# RTM_Connectors.net
KiCad netlist of a schematic drawn in Altium Designer
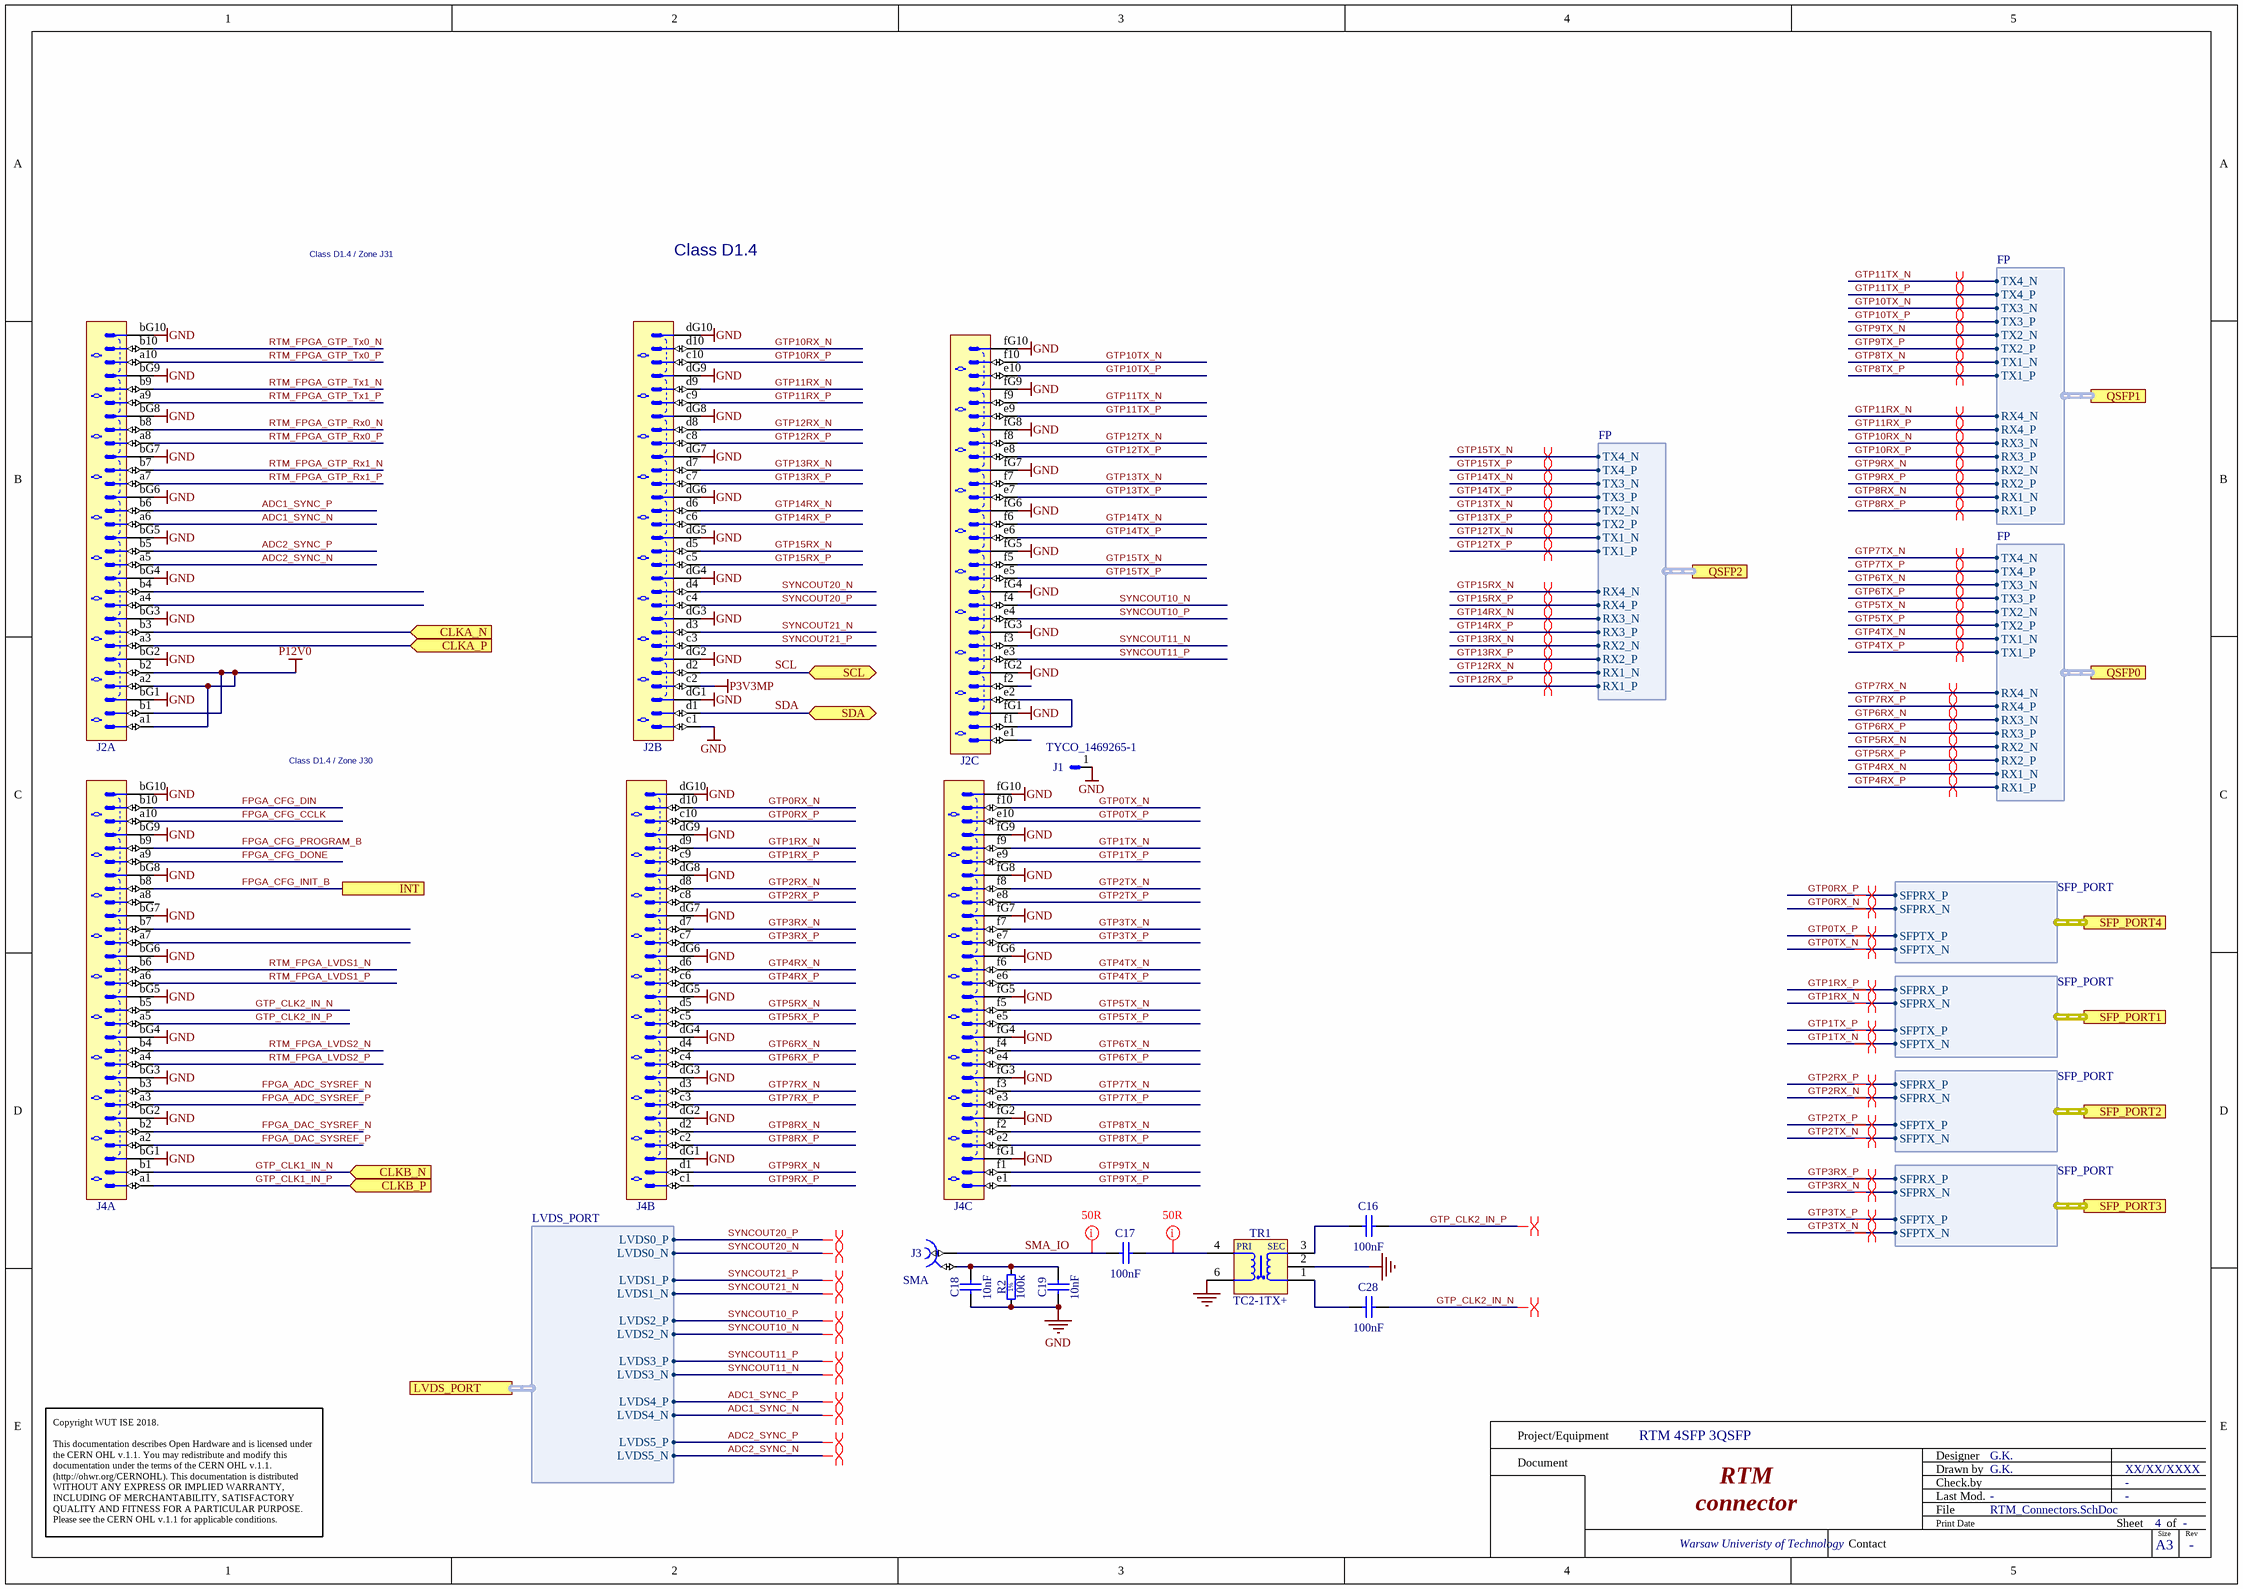
[diagram p0: RTM_Connectors.SchDoc]

(export (version "E")
  (design (tool "Eeschema 10.0.6"))
  (components
    (comp (ref "C16")
      (value "100nF")
      (footprint "CAPC0603X33N")
      (description "Non-polarised capacitor")
      (fields
        (field (name "PART NUMBER") "CC0201_100NF_6.3V_10%_X5R")
        (field (name "VOLTAGE") "6.3V")
        (field (name "AUTHOR") "CERN DEM JLC")
      )
      (libsource (lib "Capacitors") (part "Capacitor - non polarized"))
    )
    (comp (ref "C17")
      (value "100nF")
      (footprint "CAPC0603X33N")
      (description "Non-polarised capacitor")
      (fields
        (field (name "PART NUMBER") "CC0201_100NF_6.3V_10%_X5R")
        (field (name "VOLTAGE") "6.3V")
        (field (name "AUTHOR") "CERN DEM JLC")
      )
      (libsource (lib "Capacitors") (part "Capacitor - non polarized"))
    )
    (comp (ref "C18")
      (value "10nF")
      (footprint "CAPC1005X55N")
      (description "Non-polarised capacitor")
      (fields
        (field (name "PART NUMBER") "CC0402_10NF_16V_10%_X7R")
        (field (name "VOLTAGE") "16V")
        (field (name "AUTHOR") "CERN DEM JLC")
      )
      (libsource (lib "Capacitors") (part "Capacitor - non polarized"))
    )
    (comp (ref "C19")
      (value "10nF")
      (footprint "CAPC1005X55N")
      (description "Non-polarised capacitor")
      (fields
        (field (name "PART NUMBER") "CC0402_10NF_16V_10%_X7R")
        (field (name "VOLTAGE") "16V")
        (field (name "AUTHOR") "CERN DEM JLC")
      )
      (libsource (lib "Capacitors") (part "Capacitor - non polarized"))
    )
    (comp (ref "C28")
      (value "100nF")
      (footprint "CAPC0603X33N")
      (description "Non-polarised capacitor")
      (fields
        (field (name "PART NUMBER") "CC0201_100NF_6.3V_10%_X5R")
        (field (name "VOLTAGE") "6.3V")
        (field (name "AUTHOR") "CERN DEM JLC")
      )
      (libsource (lib "Capacitors") (part "Capacitor - non polarized"))
    )
    (comp (ref "J1")
      (value "TYCO_1469265-1")
      (footprint "TYCO_1469265-1")
      (description "Single Pin Male")
      (libsource (lib "Connectors") (part "Single Pin Male"))
    )
    (comp (ref "J2")
      (value "Advanced TCA")
      (footprint "TYCO_6469183-1")
      (description "Connector 60 ATCA Male 30 Pairs (60 Signals) + 3x10 Ground")
      (fields
        (field (name "PART NUMBER") "TYCO_6469183-1")
        (field (name "MANUFACTURER") "TYCO ELECTRONICS")
        (field (name "AUTHOR") "CERN DEM JLC")
      )
      (libsource (lib "Connectors") (part "Connector ATCA 60+30 Male"))
    )
    (comp (ref "J3")
      (value "SMA")
      (footprint "AMPHENOL_132203")
      (fields
        (field (name "PART NUMBER") "AMPHENOL_132203")
        (field (name "MANUFACTURER") "AMPHENOL")
        (field (name "MANUFACTURER PART NUMBER") "132203")
        (field (name "AUTHOR") "CERN DEM MR")
      )
      (libsource (lib "Connectors") (part "Coax_1Female_1Shield"))
    )
    (comp (ref "J4")
      (value "Advanced TCA")
      (footprint "TYCO_6469183-1")
      (description "Connector 60 ATCA Male 30 Pairs (60 Signals) + 3x10 Ground")
      (fields
        (field (name "PART NUMBER") "TYCO_6469183-1")
        (field (name "MANUFACTURER") "TYCO ELECTRONICS")
        (field (name "AUTHOR") "CERN DEM JLC")
      )
      (libsource (lib "Connectors") (part "Connector ATCA 60+30 Male"))
    )
    (comp (ref "R2")
      (value "100k")
      (footprint "RESC1005X40N")
      (description "Resistor - 1%")
      (fields
        (field (name "PART NUMBER") "R0402_100K_1%_0.0625W_100PPM")
        (field (name "MANUFACTURER") "GENERIC")
        (field (name "AUTHOR") "CERN DEM JLC")
      )
      (libsource (lib "Resistors") (part "Resistor - 1%"))
    )
    (comp (ref "TR1")
      (value "TC2-1TX+")
      (footprint "XFMR_MINI-CIRCUITS_AT1521")
      (description "50 Ohm 3 to 300MHz RF Transformers")
      (fields (field (name "MANUFACTURER") "MINI-CIRCUITS"))
      (libsource (lib "Schlib1") (part "XFMR_MINI-CIRCUITS_TC2-1TX+"))
    )
  )
  (nets
    (net (code "4") (name "/ADC1_SYNC_N") (class "Default")
      (node (ref "J2") (pin "a6") (pinfunction "a6_a6") (pintype "bidirectional"))
    )
    (net (code "5") (name "/ADC1_SYNC_P") (class "Default")
      (node (ref "J2") (pin "b6") (pinfunction "b6_b6") (pintype "bidirectional"))
    )
    (net (code "6") (name "/ADC2_SYNC_N") (class "Default")
      (node (ref "J2") (pin "a5") (pinfunction "a5_a5") (pintype "bidirectional"))
    )
    (net (code "7") (name "/ADC2_SYNC_P") (class "Default")
      (node (ref "J2") (pin "b5") (pinfunction "b5_b5") (pintype "bidirectional"))
    )
    (net (code "8") (name "/CLKA_N") (class "Default")
      (node (ref "J2") (pin "b3") (pinfunction "b3_b3") (pintype "bidirectional"))
    )
    (net (code "9") (name "/CLKA_P") (class "Default")
      (node (ref "J2") (pin "a3") (pinfunction "a3_a3") (pintype "bidirectional"))
    )
    (net (code "10") (name "/FPGA_ADC_SYSREF_N") (class "Default")
      (node (ref "J4") (pin "b3") (pinfunction "b3_b3") (pintype "bidirectional"))
    )
    (net (code "11") (name "/FPGA_ADC_SYSREF_P") (class "Default")
      (node (ref "J4") (pin "a3") (pinfunction "a3_a3") (pintype "bidirectional"))
    )
    (net (code "12") (name "/FPGA_CFG_CCLK") (class "Default")
      (node (ref "J4") (pin "a10") (pinfunction "a10_a10") (pintype "bidirectional"))
    )
    (net (code "13") (name "/FPGA_CFG_DIN") (class "Default")
      (node (ref "J4") (pin "b10") (pinfunction "b10_b10") (pintype "bidirectional"))
    )
    (net (code "14") (name "/FPGA_CFG_DONE") (class "Default")
      (node (ref "J4") (pin "a9") (pinfunction "a9_a9") (pintype "bidirectional"))
    )
    (net (code "15") (name "/FPGA_CFG_INIT_B") (class "Default")
      (node (ref "J4") (pin "b8") (pinfunction "b8_b8") (pintype "bidirectional"))
    )
    (net (code "16") (name "/FPGA_CFG_PROGRAM_B") (class "Default")
      (node (ref "J4") (pin "b9") (pinfunction "b9_b9") (pintype "bidirectional"))
    )
    (net (code "17") (name "/FPGA_DAC_SYSREF_N") (class "Default")
      (node (ref "J4") (pin "b2") (pinfunction "b2_b2") (pintype "bidirectional"))
    )
    (net (code "18") (name "/FPGA_DAC_SYSREF_P") (class "Default")
      (node (ref "J4") (pin "a2") (pinfunction "a2_a2") (pintype "bidirectional"))
    )
    (net (code "19") (name "/GTP0RX_N") (class "Default")
      (node (ref "J4") (pin "d10") (pinfunction "d10_d10") (pintype "bidirectional"))
    )
    (net (code "20") (name "/GTP0RX_P") (class "Default")
      (node (ref "J4") (pin "c10") (pinfunction "c10_c10") (pintype "bidirectional"))
    )
    (net (code "21") (name "/GTP0TX_N") (class "Default")
      (node (ref "J4") (pin "f10") (pinfunction "f10_f10") (pintype "bidirectional"))
    )
    (net (code "22") (name "/GTP0TX_P") (class "Default")
      (node (ref "J4") (pin "e10") (pinfunction "e10_e10") (pintype "bidirectional"))
    )
    (net (code "23") (name "/GTP1RX_N") (class "Default")
      (node (ref "J4") (pin "d9") (pinfunction "d9_d9") (pintype "bidirectional"))
    )
    (net (code "24") (name "/GTP1RX_P") (class "Default")
      (node (ref "J4") (pin "c9") (pinfunction "c9_c9") (pintype "bidirectional"))
    )
    (net (code "25") (name "/GTP1TX_N") (class "Default")
      (node (ref "J4") (pin "f9") (pinfunction "f9_f9") (pintype "bidirectional"))
    )
    (net (code "26") (name "/GTP1TX_P") (class "Default")
      (node (ref "J4") (pin "e9") (pinfunction "e9_e9") (pintype "bidirectional"))
    )
    (net (code "27") (name "/GTP2RX_N") (class "Default")
      (node (ref "J4") (pin "d8") (pinfunction "d8_d8") (pintype "bidirectional"))
    )
    (net (code "28") (name "/GTP2RX_P") (class "Default")
      (node (ref "J4") (pin "c8") (pinfunction "c8_c8") (pintype "bidirectional"))
    )
    (net (code "29") (name "/GTP2TX_N") (class "Default")
      (node (ref "J4") (pin "f8") (pinfunction "f8_f8") (pintype "bidirectional"))
    )
    (net (code "30") (name "/GTP2TX_P") (class "Default")
      (node (ref "J4") (pin "e8") (pinfunction "e8_e8") (pintype "bidirectional"))
    )
    (net (code "31") (name "/GTP3RX_N") (class "Default")
      (node (ref "J4") (pin "d7") (pinfunction "d7_d7") (pintype "bidirectional"))
    )
    (net (code "32") (name "/GTP3RX_P") (class "Default")
      (node (ref "J4") (pin "c7") (pinfunction "c7_c7") (pintype "bidirectional"))
    )
    (net (code "33") (name "/GTP3TX_N") (class "Default")
      (node (ref "J4") (pin "f7") (pinfunction "f7_f7") (pintype "bidirectional"))
    )
    (net (code "34") (name "/GTP3TX_P") (class "Default")
      (node (ref "J4") (pin "e7") (pinfunction "e7_e7") (pintype "bidirectional"))
    )
    (net (code "35") (name "/GTP4RX_N") (class "Default")
      (node (ref "J4") (pin "d6") (pinfunction "d6_d6") (pintype "bidirectional"))
    )
    (net (code "36") (name "/GTP4RX_P") (class "Default")
      (node (ref "J4") (pin "c6") (pinfunction "c6_c6") (pintype "bidirectional"))
    )
    (net (code "37") (name "/GTP4TX_N") (class "Default")
      (node (ref "J4") (pin "f6") (pinfunction "f6_f6") (pintype "bidirectional"))
    )
    (net (code "38") (name "/GTP4TX_P") (class "Default")
      (node (ref "J4") (pin "e6") (pinfunction "e6_e6") (pintype "bidirectional"))
    )
    (net (code "39") (name "/GTP5RX_N") (class "Default")
      (node (ref "J4") (pin "d5") (pinfunction "d5_d5") (pintype "bidirectional"))
    )
    (net (code "40") (name "/GTP5RX_P") (class "Default")
      (node (ref "J4") (pin "c5") (pinfunction "c5_c5") (pintype "bidirectional"))
    )
    (net (code "41") (name "/GTP5TX_N") (class "Default")
      (node (ref "J4") (pin "f5") (pinfunction "f5_f5") (pintype "bidirectional"))
    )
    (net (code "42") (name "/GTP5TX_P") (class "Default")
      (node (ref "J4") (pin "e5") (pinfunction "e5_e5") (pintype "bidirectional"))
    )
    (net (code "43") (name "/GTP6RX_N") (class "Default")
      (node (ref "J4") (pin "d4") (pinfunction "d4_d4") (pintype "bidirectional"))
    )
    (net (code "44") (name "/GTP6RX_P") (class "Default")
      (node (ref "J4") (pin "c4") (pinfunction "c4_c4") (pintype "bidirectional"))
    )
    (net (code "45") (name "/GTP6TX_N") (class "Default")
      (node (ref "J4") (pin "f4") (pinfunction "f4_f4") (pintype "bidirectional"))
    )
    (net (code "46") (name "/GTP6TX_P") (class "Default")
      (node (ref "J4") (pin "e4") (pinfunction "e4_e4") (pintype "bidirectional"))
    )
    (net (code "47") (name "/GTP7RX_N") (class "Default")
      (node (ref "J4") (pin "d3") (pinfunction "d3_d3") (pintype "bidirectional"))
    )
    (net (code "48") (name "/GTP7RX_P") (class "Default")
      (node (ref "J4") (pin "c3") (pinfunction "c3_c3") (pintype "bidirectional"))
    )
    (net (code "49") (name "/GTP7TX_N") (class "Default")
      (node (ref "J4") (pin "f3") (pinfunction "f3_f3") (pintype "bidirectional"))
    )
    (net (code "50") (name "/GTP7TX_P") (class "Default")
      (node (ref "J4") (pin "e3") (pinfunction "e3_e3") (pintype "bidirectional"))
    )
    (net (code "51") (name "/GTP8RX_N") (class "Default")
      (node (ref "J4") (pin "d2") (pinfunction "d2_d2") (pintype "bidirectional"))
    )
    (net (code "52") (name "/GTP8RX_P") (class "Default")
      (node (ref "J4") (pin "c2") (pinfunction "c2_c2") (pintype "bidirectional"))
    )
    (net (code "53") (name "/GTP8TX_N") (class "Default")
      (node (ref "J4") (pin "f2") (pinfunction "f2_f2") (pintype "bidirectional"))
    )
    (net (code "54") (name "/GTP8TX_P") (class "Default")
      (node (ref "J4") (pin "e2") (pinfunction "e2_e2") (pintype "bidirectional"))
    )
    (net (code "55") (name "/GTP9RX_N") (class "Default")
      (node (ref "J4") (pin "d1") (pinfunction "d1_d1") (pintype "bidirectional"))
    )
    (net (code "56") (name "/GTP9RX_P") (class "Default")
      (node (ref "J4") (pin "c1") (pinfunction "c1_c1") (pintype "bidirectional"))
    )
    (net (code "57") (name "/GTP9TX_N") (class "Default")
      (node (ref "J4") (pin "f1") (pinfunction "f1_f1") (pintype "bidirectional"))
    )
    (net (code "58") (name "/GTP9TX_P") (class "Default")
      (node (ref "J4") (pin "e1") (pinfunction "e1_e1") (pintype "bidirectional"))
    )
    (net (code "59") (name "/GTP10RX_N") (class "Default")
      (node (ref "J2") (pin "d10") (pinfunction "d10_d10") (pintype "bidirectional"))
    )
    (net (code "60") (name "/GTP10RX_P") (class "Default")
      (node (ref "J2") (pin "c10") (pinfunction "c10_c10") (pintype "bidirectional"))
    )
    (net (code "61") (name "/GTP10TX_N") (class "Default")
      (node (ref "J2") (pin "f10") (pinfunction "f10_f10") (pintype "bidirectional"))
    )
    (net (code "62") (name "/GTP10TX_P") (class "Default")
      (node (ref "J2") (pin "e10") (pinfunction "e10_e10") (pintype "bidirectional"))
    )
    (net (code "63") (name "/GTP11RX_N") (class "Default")
      (node (ref "J2") (pin "d9") (pinfunction "d9_d9") (pintype "bidirectional"))
    )
    (net (code "64") (name "/GTP11RX_P") (class "Default")
      (node (ref "J2") (pin "c9") (pinfunction "c9_c9") (pintype "bidirectional"))
    )
    (net (code "65") (name "/GTP11TX_N") (class "Default")
      (node (ref "J2") (pin "f9") (pinfunction "f9_f9") (pintype "bidirectional"))
    )
    (net (code "66") (name "/GTP11TX_P") (class "Default")
      (node (ref "J2") (pin "e9") (pinfunction "e9_e9") (pintype "bidirectional"))
    )
    (net (code "67") (name "/GTP12RX_N") (class "Default")
      (node (ref "J2") (pin "d8") (pinfunction "d8_d8") (pintype "bidirectional"))
    )
    (net (code "68") (name "/GTP12RX_P") (class "Default")
      (node (ref "J2") (pin "c8") (pinfunction "c8_c8") (pintype "bidirectional"))
    )
    (net (code "69") (name "/GTP12TX_N") (class "Default")
      (node (ref "J2") (pin "f8") (pinfunction "f8_f8") (pintype "bidirectional"))
    )
    (net (code "70") (name "/GTP12TX_P") (class "Default")
      (node (ref "J2") (pin "e8") (pinfunction "e8_e8") (pintype "bidirectional"))
    )
    (net (code "71") (name "/GTP13RX_N") (class "Default")
      (node (ref "J2") (pin "d7") (pinfunction "d7_d7") (pintype "bidirectional"))
    )
    (net (code "72") (name "/GTP13RX_P") (class "Default")
      (node (ref "J2") (pin "c7") (pinfunction "c7_c7") (pintype "bidirectional"))
    )
    (net (code "73") (name "/GTP13TX_N") (class "Default")
      (node (ref "J2") (pin "f7") (pinfunction "f7_f7") (pintype "bidirectional"))
    )
    (net (code "74") (name "/GTP13TX_P") (class "Default")
      (node (ref "J2") (pin "e7") (pinfunction "e7_e7") (pintype "bidirectional"))
    )
    (net (code "75") (name "/GTP14RX_N") (class "Default")
      (node (ref "J2") (pin "d6") (pinfunction "d6_d6") (pintype "bidirectional"))
    )
    (net (code "76") (name "/GTP14RX_P") (class "Default")
      (node (ref "J2") (pin "c6") (pinfunction "c6_c6") (pintype "bidirectional"))
    )
    (net (code "77") (name "/GTP14TX_N") (class "Default")
      (node (ref "J2") (pin "f6") (pinfunction "f6_f6") (pintype "bidirectional"))
    )
    (net (code "78") (name "/GTP14TX_P") (class "Default")
      (node (ref "J2") (pin "e6") (pinfunction "e6_e6") (pintype "bidirectional"))
    )
    (net (code "79") (name "/GTP15RX_N") (class "Default")
      (node (ref "J2") (pin "d5") (pinfunction "d5_d5") (pintype "bidirectional"))
    )
    (net (code "80") (name "/GTP15RX_P") (class "Default")
      (node (ref "J2") (pin "c5") (pinfunction "c5_c5") (pintype "bidirectional"))
    )
    (net (code "81") (name "/GTP15TX_N") (class "Default")
      (node (ref "J2") (pin "f5") (pinfunction "f5_f5") (pintype "bidirectional"))
    )
    (net (code "82") (name "/GTP15TX_P") (class "Default")
      (node (ref "J2") (pin "e5") (pinfunction "e5_e5") (pintype "bidirectional"))
    )
    (net (code "83") (name "/GTP_CLK1_IN_N") (class "Default")
      (node (ref "J4") (pin "b1") (pinfunction "b1_b1") (pintype "bidirectional"))
    )
    (net (code "84") (name "/GTP_CLK1_IN_P") (class "Default")
      (node (ref "J4") (pin "a1") (pinfunction "a1_a1") (pintype "bidirectional"))
    )
    (net (code "85") (name "/GTP_CLK2_IN_N") (class "Default")
      (node (ref "C28") (pin "2") (pinfunction "2_2") (pintype "passive"))
      (node (ref "J4") (pin "b5") (pinfunction "b5_b5") (pintype "bidirectional"))
    )
    (net (code "86") (name "/GTP_CLK2_IN_P") (class "Default")
      (node (ref "C16") (pin "2") (pinfunction "2_2") (pintype "passive"))
      (node (ref "J4") (pin "a5") (pinfunction "a5_a5") (pintype "bidirectional"))
    )
    (net (code "88") (name "/RTM_FPGA_GTP_Rx0_N") (class "Default")
      (node (ref "J2") (pin "b8") (pinfunction "b8_b8") (pintype "bidirectional"))
    )
    (net (code "89") (name "/RTM_FPGA_GTP_Rx0_P") (class "Default")
      (node (ref "J2") (pin "a8") (pinfunction "a8_a8") (pintype "bidirectional"))
    )
    (net (code "90") (name "/RTM_FPGA_GTP_Rx1_N") (class "Default")
      (node (ref "J2") (pin "b7") (pinfunction "b7_b7") (pintype "bidirectional"))
    )
    (net (code "91") (name "/RTM_FPGA_GTP_Rx1_P") (class "Default")
      (node (ref "J2") (pin "a7") (pinfunction "a7_a7") (pintype "bidirectional"))
    )
    (net (code "92") (name "/RTM_FPGA_GTP_Tx0_N") (class "Default")
      (node (ref "J2") (pin "b10") (pinfunction "b10_b10") (pintype "bidirectional"))
    )
    (net (code "93") (name "/RTM_FPGA_GTP_Tx0_P") (class "Default")
      (node (ref "J2") (pin "a10") (pinfunction "a10_a10") (pintype "bidirectional"))
    )
    (net (code "94") (name "/RTM_FPGA_GTP_Tx1_N") (class "Default")
      (node (ref "J2") (pin "b9") (pinfunction "b9_b9") (pintype "bidirectional"))
    )
    (net (code "95") (name "/RTM_FPGA_GTP_Tx1_P") (class "Default")
      (node (ref "J2") (pin "a9") (pinfunction "a9_a9") (pintype "bidirectional"))
    )
    (net (code "96") (name "/RTM_FPGA_LVDS1_N") (class "Default")
      (node (ref "J4") (pin "b6") (pinfunction "b6_b6") (pintype "bidirectional"))
    )
    (net (code "97") (name "/RTM_FPGA_LVDS1_P") (class "Default")
      (node (ref "J4") (pin "a6") (pinfunction "a6_a6") (pintype "bidirectional"))
    )
    (net (code "98") (name "/RTM_FPGA_LVDS2_N") (class "Default")
      (node (ref "J4") (pin "b4") (pinfunction "b4_b4") (pintype "bidirectional"))
    )
    (net (code "99") (name "/RTM_FPGA_LVDS2_P") (class "Default")
      (node (ref "J4") (pin "a4") (pinfunction "a4_a4") (pintype "bidirectional"))
    )
    (net (code "100") (name "/SCL") (class "Default")
      (node (ref "J2") (pin "d2") (pinfunction "d2_d2") (pintype "bidirectional"))
    )
    (net (code "101") (name "/SDA") (class "Default")
      (node (ref "J2") (pin "d1") (pinfunction "d1_d1") (pintype "bidirectional"))
    )
    (net (code "102") (name "/SMA_IO") (class "Default")
      (node (ref "C17") (pin "1") (pinfunction "1_1") (pintype "passive"))
      (node (ref "J3") (pin "1") (pinfunction "1_1") (pintype "bidirectional"))
    )
    (net (code "103") (name "/SYNCOUT10_N") (class "Default")
      (node (ref "J2") (pin "f4") (pinfunction "f4_f4") (pintype "bidirectional"))
    )
    (net (code "104") (name "/SYNCOUT10_P") (class "Default")
      (node (ref "J2") (pin "e4") (pinfunction "e4_e4") (pintype "bidirectional"))
    )
    (net (code "105") (name "/SYNCOUT11_N") (class "Default")
      (node (ref "J2") (pin "f3") (pinfunction "f3_f3") (pintype "bidirectional"))
    )
    (net (code "106") (name "/SYNCOUT11_P") (class "Default")
      (node (ref "J2") (pin "e3") (pinfunction "e3_e3") (pintype "bidirectional"))
    )
    (net (code "107") (name "/SYNCOUT20_N") (class "Default")
      (node (ref "J2") (pin "d4") (pinfunction "d4_d4") (pintype "bidirectional"))
    )
    (net (code "108") (name "/SYNCOUT20_P") (class "Default")
      (node (ref "J2") (pin "c4") (pinfunction "c4_c4") (pintype "bidirectional"))
    )
    (net (code "109") (name "/SYNCOUT21_N") (class "Default")
      (node (ref "J2") (pin "d3") (pinfunction "d3_d3") (pintype "bidirectional"))
    )
    (net (code "110") (name "/SYNCOUT21_P") (class "Default")
      (node (ref "J2") (pin "c3") (pinfunction "c3_c3") (pintype "bidirectional"))
    )
    (net (code "114") (name "GND") (class "Default")
      (node (ref "C18") (pin "1") (pinfunction "1_1") (pintype "passive"))
      (node (ref "C19") (pin "1") (pinfunction "1_1") (pintype "passive"))
      (node (ref "J1") (pin "1") (pinfunction "1_1") (pintype "bidirectional"))
      (node (ref "J2") (pin "bG1") (pinfunction "bG1_bG1") (pintype "power_in"))
      (node (ref "J2") (pin "bG10") (pinfunction "bG10_bG10") (pintype "power_in"))
      (node (ref "J2") (pin "bG2") (pinfunction "bG2_bG2") (pintype "power_in"))
      (node (ref "J2") (pin "bG3") (pinfunction "bG3_bG3") (pintype "power_in"))
      (node (ref "J2") (pin "bG4") (pinfunction "bG4_bG4") (pintype "power_in"))
      (node (ref "J2") (pin "bG5") (pinfunction "bG5_bG5") (pintype "power_in"))
      (node (ref "J2") (pin "bG6") (pinfunction "bG6_bG6") (pintype "power_in"))
      (node (ref "J2") (pin "bG7") (pinfunction "bG7_bG7") (pintype "power_in"))
      (node (ref "J2") (pin "bG8") (pinfunction "bG8_bG8") (pintype "power_in"))
      (node (ref "J2") (pin "bG9") (pinfunction "bG9_bG9") (pintype "power_in"))
      (node (ref "J2") (pin "c1") (pinfunction "c1_c1") (pintype "bidirectional"))
      (node (ref "J2") (pin "dG1") (pinfunction "dG1_dG1") (pintype "power_in"))
      (node (ref "J2") (pin "dG10") (pinfunction "dG10_dG10") (pintype "power_in"))
      (node (ref "J2") (pin "dG2") (pinfunction "dG2_dG2") (pintype "power_in"))
      (node (ref "J2") (pin "dG3") (pinfunction "dG3_dG3") (pintype "power_in"))
      (node (ref "J2") (pin "dG4") (pinfunction "dG4_dG4") (pintype "power_in"))
      (node (ref "J2") (pin "dG5") (pinfunction "dG5_dG5") (pintype "power_in"))
      (node (ref "J2") (pin "dG6") (pinfunction "dG6_dG6") (pintype "power_in"))
      (node (ref "J2") (pin "dG7") (pinfunction "dG7_dG7") (pintype "power_in"))
      (node (ref "J2") (pin "dG8") (pinfunction "dG8_dG8") (pintype "power_in"))
      (node (ref "J2") (pin "dG9") (pinfunction "dG9_dG9") (pintype "power_in"))
      (node (ref "J2") (pin "fG1") (pinfunction "fG1_fG1") (pintype "power_in"))
      (node (ref "J2") (pin "fG10") (pinfunction "fG10_fG10") (pintype "power_in"))
      (node (ref "J2") (pin "fG2") (pinfunction "fG2_fG2") (pintype "power_in"))
      (node (ref "J2") (pin "fG3") (pinfunction "fG3_fG3") (pintype "power_in"))
      (node (ref "J2") (pin "fG4") (pinfunction "fG4_fG4") (pintype "power_in"))
      (node (ref "J2") (pin "fG5") (pinfunction "fG5_fG5") (pintype "power_in"))
      (node (ref "J2") (pin "fG6") (pinfunction "fG6_fG6") (pintype "power_in"))
      (node (ref "J2") (pin "fG7") (pinfunction "fG7_fG7") (pintype "power_in"))
      (node (ref "J2") (pin "fG8") (pinfunction "fG8_fG8") (pintype "power_in"))
      (node (ref "J2") (pin "fG9") (pinfunction "fG9_fG9") (pintype "power_in"))
      (node (ref "J4") (pin "bG1") (pinfunction "bG1_bG1") (pintype "power_in"))
      (node (ref "J4") (pin "bG10") (pinfunction "bG10_bG10") (pintype "power_in"))
      (node (ref "J4") (pin "bG2") (pinfunction "bG2_bG2") (pintype "power_in"))
      (node (ref "J4") (pin "bG3") (pinfunction "bG3_bG3") (pintype "power_in"))
      (node (ref "J4") (pin "bG4") (pinfunction "bG4_bG4") (pintype "power_in"))
      (node (ref "J4") (pin "bG5") (pinfunction "bG5_bG5") (pintype "power_in"))
      (node (ref "J4") (pin "bG6") (pinfunction "bG6_bG6") (pintype "power_in"))
      (node (ref "J4") (pin "bG7") (pinfunction "bG7_bG7") (pintype "power_in"))
      (node (ref "J4") (pin "bG8") (pinfunction "bG8_bG8") (pintype "power_in"))
      (node (ref "J4") (pin "bG9") (pinfunction "bG9_bG9") (pintype "power_in"))
      (node (ref "J4") (pin "dG1") (pinfunction "dG1_dG1") (pintype "power_in"))
      (node (ref "J4") (pin "dG10") (pinfunction "dG10_dG10") (pintype "power_in"))
      (node (ref "J4") (pin "dG2") (pinfunction "dG2_dG2") (pintype "power_in"))
      (node (ref "J4") (pin "dG3") (pinfunction "dG3_dG3") (pintype "power_in"))
      (node (ref "J4") (pin "dG4") (pinfunction "dG4_dG4") (pintype "power_in"))
      (node (ref "J4") (pin "dG5") (pinfunction "dG5_dG5") (pintype "power_in"))
      (node (ref "J4") (pin "dG6") (pinfunction "dG6_dG6") (pintype "power_in"))
      (node (ref "J4") (pin "dG7") (pinfunction "dG7_dG7") (pintype "power_in"))
      (node (ref "J4") (pin "dG8") (pinfunction "dG8_dG8") (pintype "power_in"))
      (node (ref "J4") (pin "dG9") (pinfunction "dG9_dG9") (pintype "power_in"))
      (node (ref "J4") (pin "fG1") (pinfunction "fG1_fG1") (pintype "power_in"))
      (node (ref "J4") (pin "fG10") (pinfunction "fG10_fG10") (pintype "power_in"))
      (node (ref "J4") (pin "fG2") (pinfunction "fG2_fG2") (pintype "power_in"))
      (node (ref "J4") (pin "fG3") (pinfunction "fG3_fG3") (pintype "power_in"))
      (node (ref "J4") (pin "fG4") (pinfunction "fG4_fG4") (pintype "power_in"))
      (node (ref "J4") (pin "fG5") (pinfunction "fG5_fG5") (pintype "power_in"))
      (node (ref "J4") (pin "fG6") (pinfunction "fG6_fG6") (pintype "power_in"))
      (node (ref "J4") (pin "fG7") (pinfunction "fG7_fG7") (pintype "power_in"))
      (node (ref "J4") (pin "fG8") (pinfunction "fG8_fG8") (pintype "power_in"))
      (node (ref "J4") (pin "fG9") (pinfunction "fG9_fG9") (pintype "power_in"))
      (node (ref "R2") (pin "1") (pinfunction "1_1") (pintype "passive"))
      (node (ref "TR1") (pin "2") (pinfunction "NU_2") (pintype "passive"))
      (node (ref "TR1") (pin "6") (pinfunction "PDOT_6") (pintype "passive"))
    )
    (net (code "115") (name "Net-(C18-Pad2)") (class "Default")
      (node (ref "C18") (pin "2") (pinfunction "2_2") (pintype "passive"))
      (node (ref "C19") (pin "2") (pinfunction "2_2") (pintype "passive"))
      (node (ref "J3") (pin "2") (pinfunction "2_2") (pintype "bidirectional"))
      (node (ref "R2") (pin "2") (pinfunction "2_2") (pintype "passive"))
    )
    (net (code "116") (name "Net-(J2-Pade2)") (class "Default")
      (node (ref "J2") (pin "e2") (pinfunction "e2_e2") (pintype "bidirectional"))
      (node (ref "J2") (pin "f1") (pinfunction "f1_f1") (pintype "bidirectional"))
    )
    (net (code "117") (name "Net-(TR1-P)") (class "Default")
      (node (ref "C17") (pin "2") (pinfunction "2_2") (pintype "passive"))
      (node (ref "TR1") (pin "4") (pinfunction "P_4") (pintype "passive"))
    )
    (net (code "118") (name "Net-(TR1-S)") (class "Default")
      (node (ref "C16") (pin "1") (pinfunction "1_1") (pintype "passive"))
      (node (ref "TR1") (pin "3") (pinfunction "S_3") (pintype "passive"))
    )
    (net (code "119") (name "Net-(TR1-SDOT)") (class "Default")
      (node (ref "C28") (pin "1") (pinfunction "1_1") (pintype "passive"))
      (node (ref "TR1") (pin "1") (pinfunction "SDOT_1") (pintype "passive"))
    )
    (net (code "120") (name "P3V3MP") (class "Default")
      (node (ref "J2") (pin "c2") (pinfunction "c2_c2") (pintype "bidirectional"))
    )
    (net (code "121") (name "P12V0") (class "Default")
      (node (ref "J2") (pin "a1") (pinfunction "a1_a1") (pintype "bidirectional"))
      (node (ref "J2") (pin "a2") (pinfunction "a2_a2") (pintype "bidirectional"))
      (node (ref "J2") (pin "b1") (pinfunction "b1_b1") (pintype "bidirectional"))
      (node (ref "J2") (pin "b2") (pinfunction "b2_b2") (pintype "bidirectional"))
    )
    (net (code "122") (name "unconnected-(J2-Pada4)") (class "Default")
      (node (ref "J2") (pin "a4") (pinfunction "a4_a4") (pintype "bidirectional"))
    )
    (net (code "123") (name "unconnected-(J2-Padb4)") (class "Default")
      (node (ref "J2") (pin "b4") (pinfunction "b4_b4") (pintype "bidirectional"))
    )
    (net (code "124") (name "unconnected-(J2-Pade1)") (class "Default")
      (node (ref "J2") (pin "e1") (pinfunction "e1_e1") (pintype "bidirectional"))
    )
    (net (code "125") (name "unconnected-(J2-Padf2)") (class "Default")
      (node (ref "J2") (pin "f2") (pinfunction "f2_f2") (pintype "bidirectional"))
    )
    (net (code "126") (name "unconnected-(J4-Pada7)") (class "Default")
      (node (ref "J4") (pin "a7") (pinfunction "a7_a7") (pintype "bidirectional"))
    )
    (net (code "127") (name "unconnected-(J4-Pada8)") (class "Default")
      (node (ref "J4") (pin "a8") (pinfunction "a8_a8") (pintype "bidirectional"))
    )
    (net (code "128") (name "unconnected-(J4-Padb7)") (class "Default")
      (node (ref "J4") (pin "b7") (pinfunction "b7_b7") (pintype "bidirectional"))
    )
  )
)
